# LEDcontroller.net
KiCad netlist of a schematic drawn in EAGLE
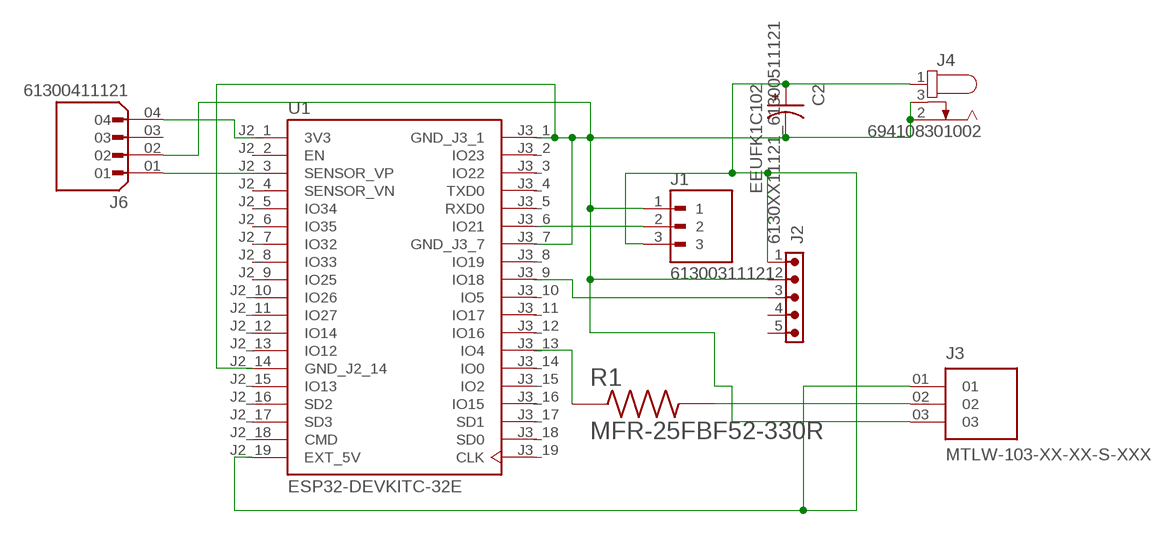
[diagram p0: schematic, sheet 1]

(export (version "E")
  (design (tool "Eeschema 10.0.6"))
  (components
    (comp (ref "C2")
      (value "EEUFK1C102")
      (footprint "eagle-import:CAPPRD500W60D1000H1600")
      (fields (field (name "MF") "Panasonic Electronic Components") (field (name "MP") "EEU-FK1C102"))
      (libsource (lib "eagle-import") (part "EEUFK1C102"))
    )
    (comp (ref "J1")
      (value "61300311121")
      (footprint "eagle-import:WURTH_61300311121")
      (fields (field (name "DIGIKEY_PART_NUMBER") "732-5316-ND") (field (name "MF") "Wurth Electronics"))
      (libsource (lib "eagle-import") (part "61300311121"))
    )
    (comp (ref "J2")
      (value "6130XX11121_61300511121")
      (footprint "eagle-import:61300511121")
      (fields
        (field (name "DIGIKEY_PART_NUMBER") "732-5318-ND")
        (field (name "MF") "Wurth Electronics")
        (field (name "MP") "61300511121")
      )
      (libsource (lib "eagle-import") (part "6130XX11121_61300511121"))
    )
    (comp (ref "J3")
      (value "MTLW-103-XX-XX-S-XXX")
      (footprint "eagle-import:SAMTEC_MTLW-103-XX-XX-S-XXX")
      (fields
        (field (name "DIGIKEY_PART_NUMBER") "SAM11546-ND")
        (field (name "MF") "Samtec")
        (field (name "MP") "MTLW-103-07-G-S-230")
      )
      (libsource (lib "eagle-import") (part "MTLW-103-XX-XX-S-XXX"))
    )
    (comp (ref "J4")
      (value "694108301002")
      (footprint "eagle-import:694108301002")
      (fields (field (name "DIGIKEY_PART_NUMBER") "732-5934-ND") (field (name "MF") "Würth Elektronik"))
      (libsource (lib "eagle-import") (part "694108301002"))
    )
    (comp (ref "J6")
      (value "61300411121")
      (footprint "eagle-import:WURTH_61300411121")
      (fields (field (name "DIGIKEY_PART_NUMBER") "732-5317-ND") (field (name "MF") "Wurth Electronics"))
      (libsource (lib "eagle-import") (part "61300411121"))
    )
    (comp (ref "R1")
      (value "MFR-25FBF52-330R")
      (footprint "eagle-import:RESAD1100W55L680D260")
      (fields
        (field (name "MF") "Yageo")
        (field (name "MP") "MFR-25FBF52-1K")
        (field (name "MP_1") "MFR-25FBF52-330R")
        (field (name "SNAPEDA_LINK") "https://www.snapeda.com/parts/MFR-25FBF52-330R/Yageo/view-part/?ref=eda")
      )
      (libsource (lib "eagle-import") (part "MFR-25FBF52-1K"))
    )
    (comp (ref "U1")
      (value "ESP32-DEVKITC-32E")
      (footprint "eagle-import:MODULE_ESP32-DEVKITC-32E")
      (fields (field (name "MF") "Espressif Systems"))
      (libsource (lib "eagle-import") (part "ESP32-DEVKITC-32E"))
    )
  )
  (nets
    (net (code "1") (name "Net-(J3-Pad02)") (class "Default")
      (node (ref "J3") (pin "02") (pinfunction "02_02") (pintype "passive"))
      (node (ref "R1") (pin "2") (pinfunction "2_2") (pintype "passive"))
    )
    (net (code "2") (name "Net-(U1-3V3)") (class "Default")
      (node (ref "J6") (pin "04") (pinfunction "04_04") (pintype "passive"))
      (node (ref "U1") (pin "J2_1") (pinfunction "3V3_J2_1") (pintype "power_in"))
    )
    (net (code "3") (name "Net-(U1-EXT_5V)") (class "Default")
      (node (ref "C2") (pin "P") (pinfunction "P_P") (pintype "passive"))
      (node (ref "J1") (pin "3") (pinfunction "3_3") (pintype "passive"))
      (node (ref "J2") (pin "1") (pinfunction "1_1") (pintype "passive"))
      (node (ref "J3") (pin "01") (pinfunction "01_01") (pintype "passive"))
      (node (ref "J4") (pin "1") (pinfunction "1_1") (pintype "passive"))
      (node (ref "U1") (pin "J2_19") (pinfunction "EXT_5V_J2_19") (pintype "power_in"))
    )
    (net (code "4") (name "Net-(U1-GND_J2_14)") (class "Default")
      (node (ref "C2") (pin "N") (pinfunction "N_N") (pintype "passive"))
      (node (ref "J1") (pin "1") (pinfunction "1_1") (pintype "passive"))
      (node (ref "J2") (pin "2") (pinfunction "2_2") (pintype "passive"))
      (node (ref "J3") (pin "03") (pinfunction "03_03") (pintype "passive"))
      (node (ref "J4") (pin "2") (pinfunction "2_2") (pintype "passive"))
      (node (ref "J4") (pin "3") (pinfunction "3_3") (pintype "passive"))
      (node (ref "J6") (pin "02") (pinfunction "02_02") (pintype "passive"))
      (node (ref "U1") (pin "J2_14") (pinfunction "GND_J2_14_J2_14") (pintype "power_in"))
      (node (ref "U1") (pin "J3_1") (pinfunction "GND_J3_1_J3_1") (pintype "power_in"))
      (node (ref "U1") (pin "J3_7") (pinfunction "GND_J3_7_J3_7") (pintype "power_in"))
    )
    (net (code "5") (name "Net-(U1-IO4)") (class "Default")
      (node (ref "R1") (pin "1") (pinfunction "1_1") (pintype "passive"))
      (node (ref "U1") (pin "J3_13") (pinfunction "IO4_J3_13") (pintype "bidirectional"))
    )
    (net (code "6") (name "Net-(U1-IO18)") (class "Default")
      (node (ref "J2") (pin "3") (pinfunction "3_3") (pintype "passive"))
      (node (ref "U1") (pin "J3_9") (pinfunction "IO18_J3_9") (pintype "bidirectional"))
    )
    (net (code "7") (name "Net-(U1-IO21)") (class "Default")
      (node (ref "J1") (pin "2") (pinfunction "2_2") (pintype "passive"))
      (node (ref "U1") (pin "J3_6") (pinfunction "IO21_J3_6") (pintype "bidirectional"))
    )
    (net (code "8") (name "Net-(U1-SENSOR_VP)") (class "Default")
      (node (ref "J6") (pin "01") (pinfunction "01_01") (pintype "passive"))
      (node (ref "U1") (pin "J2_3") (pinfunction "SENSOR_VP_J2_3") (pintype "bidirectional"))
    )
    (net (code "9") (name "unconnected-(J2-Pad4)") (class "Default")
      (node (ref "J2") (pin "4") (pinfunction "4_4") (pintype "passive"))
    )
    (net (code "10") (name "unconnected-(J2-Pad5)") (class "Default")
      (node (ref "J2") (pin "5") (pinfunction "5_5") (pintype "passive"))
    )
    (net (code "11") (name "unconnected-(J6-Pad03)") (class "Default")
      (node (ref "J6") (pin "03") (pinfunction "03_03") (pintype "passive"))
    )
    (net (code "12") (name "unconnected-(U1-CLK-PadJ3_19)") (class "Default")
      (node (ref "U1") (pin "J3_19") (pinfunction "CLK_J3_19") (pintype "bidirectional"))
    )
    (net (code "13") (name "unconnected-(U1-CMD-PadJ2_18)") (class "Default")
      (node (ref "U1") (pin "J2_18") (pinfunction "CMD_J2_18") (pintype "bidirectional"))
    )
    (net (code "14") (name "unconnected-(U1-EN-PadJ2_2)") (class "Default")
      (node (ref "U1") (pin "J2_2") (pinfunction "EN_J2_2") (pintype "input"))
    )
    (net (code "15") (name "unconnected-(U1-IO0-PadJ3_14)") (class "Default")
      (node (ref "U1") (pin "J3_14") (pinfunction "IO0_J3_14") (pintype "bidirectional"))
    )
    (net (code "16") (name "unconnected-(U1-IO2-PadJ3_15)") (class "Default")
      (node (ref "U1") (pin "J3_15") (pinfunction "IO2_J3_15") (pintype "bidirectional"))
    )
    (net (code "17") (name "unconnected-(U1-IO5-PadJ3_10)") (class "Default")
      (node (ref "U1") (pin "J3_10") (pinfunction "IO5_J3_10") (pintype "bidirectional"))
    )
    (net (code "18") (name "unconnected-(U1-IO12-PadJ2_13)") (class "Default")
      (node (ref "U1") (pin "J2_13") (pinfunction "IO12_J2_13") (pintype "bidirectional"))
    )
    (net (code "19") (name "unconnected-(U1-IO13-PadJ2_15)") (class "Default")
      (node (ref "U1") (pin "J2_15") (pinfunction "IO13_J2_15") (pintype "bidirectional"))
    )
    (net (code "20") (name "unconnected-(U1-IO14-PadJ2_12)") (class "Default")
      (node (ref "U1") (pin "J2_12") (pinfunction "IO14_J2_12") (pintype "bidirectional"))
    )
    (net (code "21") (name "unconnected-(U1-IO15-PadJ3_16)") (class "Default")
      (node (ref "U1") (pin "J3_16") (pinfunction "IO15_J3_16") (pintype "bidirectional"))
    )
    (net (code "22") (name "unconnected-(U1-IO16-PadJ3_12)") (class "Default")
      (node (ref "U1") (pin "J3_12") (pinfunction "IO16_J3_12") (pintype "bidirectional"))
    )
    (net (code "23") (name "unconnected-(U1-IO17-PadJ3_11)") (class "Default")
      (node (ref "U1") (pin "J3_11") (pinfunction "IO17_J3_11") (pintype "bidirectional"))
    )
    (net (code "24") (name "unconnected-(U1-IO19-PadJ3_8)") (class "Default")
      (node (ref "U1") (pin "J3_8") (pinfunction "IO19_J3_8") (pintype "bidirectional"))
    )
    (net (code "25") (name "unconnected-(U1-IO22-PadJ3_3)") (class "Default")
      (node (ref "U1") (pin "J3_3") (pinfunction "IO22_J3_3") (pintype "bidirectional"))
    )
    (net (code "26") (name "unconnected-(U1-IO23-PadJ3_2)") (class "Default")
      (node (ref "U1") (pin "J3_2") (pinfunction "IO23_J3_2") (pintype "bidirectional"))
    )
    (net (code "27") (name "unconnected-(U1-IO25-PadJ2_9)") (class "Default")
      (node (ref "U1") (pin "J2_9") (pinfunction "IO25_J2_9") (pintype "bidirectional"))
    )
    (net (code "28") (name "unconnected-(U1-IO26-PadJ2_10)") (class "Default")
      (node (ref "U1") (pin "J2_10") (pinfunction "IO26_J2_10") (pintype "bidirectional"))
    )
    (net (code "29") (name "unconnected-(U1-IO27-PadJ2_11)") (class "Default")
      (node (ref "U1") (pin "J2_11") (pinfunction "IO27_J2_11") (pintype "bidirectional"))
    )
    (net (code "30") (name "unconnected-(U1-IO32-PadJ2_7)") (class "Default")
      (node (ref "U1") (pin "J2_7") (pinfunction "IO32_J2_7") (pintype "bidirectional"))
    )
    (net (code "31") (name "unconnected-(U1-IO33-PadJ2_8)") (class "Default")
      (node (ref "U1") (pin "J2_8") (pinfunction "IO33_J2_8") (pintype "bidirectional"))
    )
    (net (code "32") (name "unconnected-(U1-IO34-PadJ2_5)") (class "Default")
      (node (ref "U1") (pin "J2_5") (pinfunction "IO34_J2_5") (pintype "bidirectional"))
    )
    (net (code "33") (name "unconnected-(U1-IO35-PadJ2_6)") (class "Default")
      (node (ref "U1") (pin "J2_6") (pinfunction "IO35_J2_6") (pintype "bidirectional"))
    )
    (net (code "34") (name "unconnected-(U1-RXD0-PadJ3_5)") (class "Default")
      (node (ref "U1") (pin "J3_5") (pinfunction "RXD0_J3_5") (pintype "bidirectional"))
    )
    (net (code "35") (name "unconnected-(U1-SD0-PadJ3_18)") (class "Default")
      (node (ref "U1") (pin "J3_18") (pinfunction "SD0_J3_18") (pintype "bidirectional"))
    )
    (net (code "36") (name "unconnected-(U1-SD1-PadJ3_17)") (class "Default")
      (node (ref "U1") (pin "J3_17") (pinfunction "SD1_J3_17") (pintype "bidirectional"))
    )
    (net (code "37") (name "unconnected-(U1-SD2-PadJ2_16)") (class "Default")
      (node (ref "U1") (pin "J2_16") (pinfunction "SD2_J2_16") (pintype "bidirectional"))
    )
    (net (code "38") (name "unconnected-(U1-SD3-PadJ2_17)") (class "Default")
      (node (ref "U1") (pin "J2_17") (pinfunction "SD3_J2_17") (pintype "bidirectional"))
    )
    (net (code "39") (name "unconnected-(U1-SENSOR_VN-PadJ2_4)") (class "Default")
      (node (ref "U1") (pin "J2_4") (pinfunction "SENSOR_VN_J2_4") (pintype "bidirectional"))
    )
    (net (code "40") (name "unconnected-(U1-TXD0-PadJ3_4)") (class "Default")
      (node (ref "U1") (pin "J3_4") (pinfunction "TXD0_J3_4") (pintype "bidirectional"))
    )
  )
)
